# digital_io.net
KiCad netlist of a schematic drawn in Altium Designer
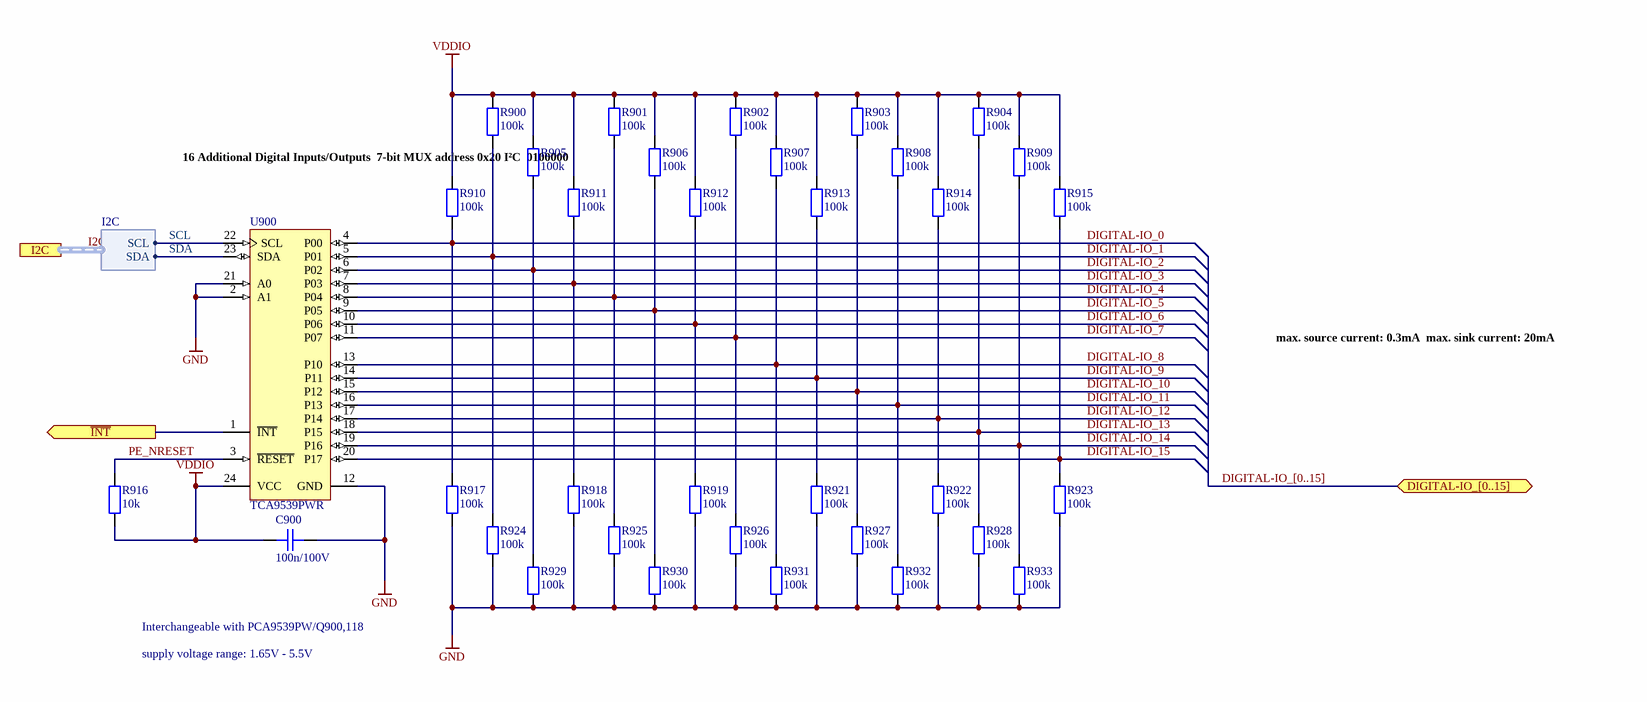
[diagram p0: digital_io.SchDoc]

(export (version "E")
  (design (tool "Eeschema 10.0.6"))
  (components
    (comp (ref "C900")
      (value "100n/100V")
      (footprint "CAPC1608X08N")
      (description "MLCC")
      (fields (field (name "PART NUMBER") "gen_C_ceramic_100n_100V_X7R_0603"))
      (libsource (lib "OE750") (part "C"))
    )
    (comp (ref "R900")
      (value "100k")
      (footprint "RESC1608X05N")
      (description "SMD Resistor 100k 0603")
      (fields (field (name "PART NUMBER") "gen_R_100k_0603") (field (name "TOLERANCE") "1%"))
      (libsource (lib "OE750") (part "R"))
    )
    (comp (ref "R901")
      (value "100k")
      (footprint "RESC1608X05N")
      (description "SMD Resistor 100k 0603")
      (fields (field (name "PART NUMBER") "gen_R_100k_0603") (field (name "TOLERANCE") "1%"))
      (libsource (lib "OE750") (part "R"))
    )
    (comp (ref "R902")
      (value "100k")
      (footprint "RESC1608X05N")
      (description "SMD Resistor 100k 0603")
      (fields (field (name "PART NUMBER") "gen_R_100k_0603") (field (name "TOLERANCE") "1%"))
      (libsource (lib "OE750") (part "R"))
    )
    (comp (ref "R903")
      (value "100k")
      (footprint "RESC1608X05N")
      (description "SMD Resistor 100k 0603")
      (fields (field (name "PART NUMBER") "gen_R_100k_0603") (field (name "TOLERANCE") "1%"))
      (libsource (lib "OE750") (part "R"))
    )
    (comp (ref "R904")
      (value "100k")
      (footprint "RESC1608X05N")
      (description "SMD Resistor 100k 0603")
      (fields (field (name "PART NUMBER") "gen_R_100k_0603") (field (name "TOLERANCE") "1%"))
      (libsource (lib "OE750") (part "R"))
    )
    (comp (ref "R905")
      (value "100k")
      (footprint "RESC1608X05N")
      (description "SMD Resistor 100k 0603")
      (fields (field (name "PART NUMBER") "gen_R_100k_0603") (field (name "TOLERANCE") "1%"))
      (libsource (lib "OE750") (part "R"))
    )
    (comp (ref "R906")
      (value "100k")
      (footprint "RESC1608X05N")
      (description "SMD Resistor 100k 0603")
      (fields (field (name "PART NUMBER") "gen_R_100k_0603") (field (name "TOLERANCE") "1%"))
      (libsource (lib "OE750") (part "R"))
    )
    (comp (ref "R907")
      (value "100k")
      (footprint "RESC1608X05N")
      (description "SMD Resistor 100k 0603")
      (fields (field (name "PART NUMBER") "gen_R_100k_0603") (field (name "TOLERANCE") "1%"))
      (libsource (lib "OE750") (part "R"))
    )
    (comp (ref "R908")
      (value "100k")
      (footprint "RESC1608X05N")
      (description "SMD Resistor 100k 0603")
      (fields (field (name "PART NUMBER") "gen_R_100k_0603") (field (name "TOLERANCE") "1%"))
      (libsource (lib "OE750") (part "R"))
    )
    (comp (ref "R909")
      (value "100k")
      (footprint "RESC1608X05N")
      (description "SMD Resistor 100k 0603")
      (fields (field (name "PART NUMBER") "gen_R_100k_0603") (field (name "TOLERANCE") "1%"))
      (libsource (lib "OE750") (part "R"))
    )
    (comp (ref "R910")
      (value "100k")
      (footprint "RESC1608X05N")
      (description "SMD Resistor 100k 0603")
      (fields (field (name "PART NUMBER") "gen_R_100k_0603") (field (name "TOLERANCE") "1%"))
      (libsource (lib "OE750") (part "R"))
    )
    (comp (ref "R911")
      (value "100k")
      (footprint "RESC1608X05N")
      (description "SMD Resistor 100k 0603")
      (fields (field (name "PART NUMBER") "gen_R_100k_0603") (field (name "TOLERANCE") "1%"))
      (libsource (lib "OE750") (part "R"))
    )
    (comp (ref "R912")
      (value "100k")
      (footprint "RESC1608X05N")
      (description "SMD Resistor 100k 0603")
      (fields (field (name "PART NUMBER") "gen_R_100k_0603") (field (name "TOLERANCE") "1%"))
      (libsource (lib "OE750") (part "R"))
    )
    (comp (ref "R913")
      (value "100k")
      (footprint "RESC1608X05N")
      (description "SMD Resistor 100k 0603")
      (fields (field (name "PART NUMBER") "gen_R_100k_0603") (field (name "TOLERANCE") "1%"))
      (libsource (lib "OE750") (part "R"))
    )
    (comp (ref "R914")
      (value "100k")
      (footprint "RESC1608X05N")
      (description "SMD Resistor 100k 0603")
      (fields (field (name "PART NUMBER") "gen_R_100k_0603") (field (name "TOLERANCE") "1%"))
      (libsource (lib "OE750") (part "R"))
    )
    (comp (ref "R915")
      (value "100k")
      (footprint "RESC1608X05N")
      (description "SMD Resistor 100k 0603")
      (fields (field (name "PART NUMBER") "gen_R_100k_0603") (field (name "TOLERANCE") "1%"))
      (libsource (lib "OE750") (part "R"))
    )
    (comp (ref "R916")
      (value "10k")
      (footprint "RESC1608X05N")
      (description "SMD Resistor 10k 0603")
      (fields (field (name "PART NUMBER") "gen_R_10k_0603") (field (name "TOLERANCE") "1%"))
      (libsource (lib "OE750") (part "R"))
    )
    (comp (ref "R917")
      (value "100k")
      (footprint "RESC1608X05N")
      (description "SMD Resistor 100k 0603")
      (fields (field (name "PART NUMBER") "gen_R_100k_0603") (field (name "TOLERANCE") "1%"))
      (libsource (lib "OE750") (part "R"))
    )
    (comp (ref "R918")
      (value "100k")
      (footprint "RESC1608X05N")
      (description "SMD Resistor 100k 0603")
      (fields (field (name "PART NUMBER") "gen_R_100k_0603") (field (name "TOLERANCE") "1%"))
      (libsource (lib "OE750") (part "R"))
    )
    (comp (ref "R919")
      (value "100k")
      (footprint "RESC1608X05N")
      (description "SMD Resistor 100k 0603")
      (fields (field (name "PART NUMBER") "gen_R_100k_0603") (field (name "TOLERANCE") "1%"))
      (libsource (lib "OE750") (part "R"))
    )
    (comp (ref "R921")
      (value "100k")
      (footprint "RESC1608X05N")
      (description "SMD Resistor 100k 0603")
      (fields (field (name "PART NUMBER") "gen_R_100k_0603") (field (name "TOLERANCE") "1%"))
      (libsource (lib "OE750") (part "R"))
    )
    (comp (ref "R922")
      (value "100k")
      (footprint "RESC1608X05N")
      (description "SMD Resistor 100k 0603")
      (fields (field (name "PART NUMBER") "gen_R_100k_0603") (field (name "TOLERANCE") "1%"))
      (libsource (lib "OE750") (part "R"))
    )
    (comp (ref "R923")
      (value "100k")
      (footprint "RESC1608X05N")
      (description "SMD Resistor 100k 0603")
      (fields (field (name "PART NUMBER") "gen_R_100k_0603") (field (name "TOLERANCE") "1%"))
      (libsource (lib "OE750") (part "R"))
    )
    (comp (ref "R924")
      (value "100k")
      (footprint "RESC1608X05N")
      (description "SMD Resistor 100k 0603")
      (fields (field (name "PART NUMBER") "gen_R_100k_0603") (field (name "TOLERANCE") "1%"))
      (libsource (lib "OE750") (part "R"))
    )
    (comp (ref "R925")
      (value "100k")
      (footprint "RESC1608X05N")
      (description "SMD Resistor 100k 0603")
      (fields (field (name "PART NUMBER") "gen_R_100k_0603") (field (name "TOLERANCE") "1%"))
      (libsource (lib "OE750") (part "R"))
    )
    (comp (ref "R926")
      (value "100k")
      (footprint "RESC1608X05N")
      (description "SMD Resistor 100k 0603")
      (fields (field (name "PART NUMBER") "gen_R_100k_0603") (field (name "TOLERANCE") "1%"))
      (libsource (lib "OE750") (part "R"))
    )
    (comp (ref "R927")
      (value "100k")
      (footprint "RESC1608X05N")
      (description "SMD Resistor 100k 0603")
      (fields (field (name "PART NUMBER") "gen_R_100k_0603") (field (name "TOLERANCE") "1%"))
      (libsource (lib "OE750") (part "R"))
    )
    (comp (ref "R928")
      (value "100k")
      (footprint "RESC1608X05N")
      (description "SMD Resistor 100k 0603")
      (fields (field (name "PART NUMBER") "gen_R_100k_0603") (field (name "TOLERANCE") "1%"))
      (libsource (lib "OE750") (part "R"))
    )
    (comp (ref "R929")
      (value "100k")
      (footprint "RESC1608X05N")
      (description "SMD Resistor 100k 0603")
      (fields (field (name "PART NUMBER") "gen_R_100k_0603") (field (name "TOLERANCE") "1%"))
      (libsource (lib "OE750") (part "R"))
    )
    (comp (ref "R930")
      (value "100k")
      (footprint "RESC1608X05N")
      (description "SMD Resistor 100k 0603")
      (fields (field (name "PART NUMBER") "gen_R_100k_0603") (field (name "TOLERANCE") "1%"))
      (libsource (lib "OE750") (part "R"))
    )
    (comp (ref "R931")
      (value "100k")
      (footprint "RESC1608X05N")
      (description "SMD Resistor 100k 0603")
      (fields (field (name "PART NUMBER") "gen_R_100k_0603") (field (name "TOLERANCE") "1%"))
      (libsource (lib "OE750") (part "R"))
    )
    (comp (ref "R932")
      (value "100k")
      (footprint "RESC1608X05N")
      (description "SMD Resistor 100k 0603")
      (fields (field (name "PART NUMBER") "gen_R_100k_0603") (field (name "TOLERANCE") "1%"))
      (libsource (lib "OE750") (part "R"))
    )
    (comp (ref "R933")
      (value "100k")
      (footprint "RESC1608X05N")
      (description "SMD Resistor 100k 0603")
      (fields (field (name "PART NUMBER") "gen_R_100k_0603") (field (name "TOLERANCE") "1%"))
      (libsource (lib "OE750") (part "R"))
    )
    (comp (ref "U900")
      (value "TCA9539PWR")
      (footprint "PW0024A_M")
      (fields (field (name "MANUFACTURER") "Texas Instruments"))
      (libsource (lib "Altium Content Vault") (part "TI-TCA9539-TSSOP_PW-24"))
    )
  )
  (nets
    (net (code "2") (name "/DIGITAL-IO_0") (class "Default")
      (node (ref "R910") (pin "1") (pinfunction "1_1") (pintype "passive"))
      (node (ref "R917") (pin "2") (pinfunction "2_2") (pintype "passive"))
      (node (ref "U900") (pin "4") (pinfunction "P00_4") (pintype "bidirectional"))
    )
    (net (code "3") (name "/DIGITAL-IO_1") (class "Default")
      (node (ref "R900") (pin "1") (pinfunction "1_1") (pintype "passive"))
      (node (ref "R924") (pin "2") (pinfunction "2_2") (pintype "passive"))
      (node (ref "U900") (pin "5") (pinfunction "P01_5") (pintype "bidirectional"))
    )
    (net (code "4") (name "/DIGITAL-IO_2") (class "Default")
      (node (ref "R905") (pin "1") (pinfunction "1_1") (pintype "passive"))
      (node (ref "R929") (pin "2") (pinfunction "2_2") (pintype "passive"))
      (node (ref "U900") (pin "6") (pinfunction "P02_6") (pintype "bidirectional"))
    )
    (net (code "5") (name "/DIGITAL-IO_3") (class "Default")
      (node (ref "R911") (pin "1") (pinfunction "1_1") (pintype "passive"))
      (node (ref "R918") (pin "2") (pinfunction "2_2") (pintype "passive"))
      (node (ref "U900") (pin "7") (pinfunction "P03_7") (pintype "bidirectional"))
    )
    (net (code "6") (name "/DIGITAL-IO_4") (class "Default")
      (node (ref "R901") (pin "1") (pinfunction "1_1") (pintype "passive"))
      (node (ref "R925") (pin "2") (pinfunction "2_2") (pintype "passive"))
      (node (ref "U900") (pin "8") (pinfunction "P04_8") (pintype "bidirectional"))
    )
    (net (code "7") (name "/DIGITAL-IO_5") (class "Default")
      (node (ref "R906") (pin "1") (pinfunction "1_1") (pintype "passive"))
      (node (ref "R930") (pin "2") (pinfunction "2_2") (pintype "passive"))
      (node (ref "U900") (pin "9") (pinfunction "P05_9") (pintype "bidirectional"))
    )
    (net (code "8") (name "/DIGITAL-IO_6") (class "Default")
      (node (ref "R912") (pin "1") (pinfunction "1_1") (pintype "passive"))
      (node (ref "R919") (pin "2") (pinfunction "2_2") (pintype "passive"))
      (node (ref "U900") (pin "10") (pinfunction "P06_10") (pintype "bidirectional"))
    )
    (net (code "9") (name "/DIGITAL-IO_7") (class "Default")
      (node (ref "R902") (pin "1") (pinfunction "1_1") (pintype "passive"))
      (node (ref "R926") (pin "2") (pinfunction "2_2") (pintype "passive"))
      (node (ref "U900") (pin "11") (pinfunction "P07_11") (pintype "bidirectional"))
    )
    (net (code "10") (name "/DIGITAL-IO_8") (class "Default")
      (node (ref "R907") (pin "1") (pinfunction "1_1") (pintype "passive"))
      (node (ref "R931") (pin "2") (pinfunction "2_2") (pintype "passive"))
      (node (ref "U900") (pin "13") (pinfunction "P10_13") (pintype "bidirectional"))
    )
    (net (code "11") (name "/DIGITAL-IO_9") (class "Default")
      (node (ref "R913") (pin "1") (pinfunction "1_1") (pintype "passive"))
      (node (ref "R921") (pin "2") (pinfunction "2_2") (pintype "passive"))
      (node (ref "U900") (pin "14") (pinfunction "P11_14") (pintype "bidirectional"))
    )
    (net (code "12") (name "/DIGITAL-IO_10") (class "Default")
      (node (ref "R903") (pin "1") (pinfunction "1_1") (pintype "passive"))
      (node (ref "R927") (pin "2") (pinfunction "2_2") (pintype "passive"))
      (node (ref "U900") (pin "15") (pinfunction "P12_15") (pintype "bidirectional"))
    )
    (net (code "13") (name "/DIGITAL-IO_11") (class "Default")
      (node (ref "R908") (pin "1") (pinfunction "1_1") (pintype "passive"))
      (node (ref "R932") (pin "2") (pinfunction "2_2") (pintype "passive"))
      (node (ref "U900") (pin "16") (pinfunction "P13_16") (pintype "bidirectional"))
    )
    (net (code "14") (name "/DIGITAL-IO_12") (class "Default")
      (node (ref "R914") (pin "1") (pinfunction "1_1") (pintype "passive"))
      (node (ref "R922") (pin "2") (pinfunction "2_2") (pintype "passive"))
      (node (ref "U900") (pin "17") (pinfunction "P14_17") (pintype "bidirectional"))
    )
    (net (code "15") (name "/DIGITAL-IO_13") (class "Default")
      (node (ref "R904") (pin "1") (pinfunction "1_1") (pintype "passive"))
      (node (ref "R928") (pin "2") (pinfunction "2_2") (pintype "passive"))
      (node (ref "U900") (pin "18") (pinfunction "P15_18") (pintype "bidirectional"))
    )
    (net (code "16") (name "/DIGITAL-IO_14") (class "Default")
      (node (ref "R909") (pin "1") (pinfunction "1_1") (pintype "passive"))
      (node (ref "R933") (pin "2") (pinfunction "2_2") (pintype "passive"))
      (node (ref "U900") (pin "19") (pinfunction "P16_19") (pintype "bidirectional"))
    )
    (net (code "17") (name "/DIGITAL-IO_15") (class "Default")
      (node (ref "R915") (pin "1") (pinfunction "1_1") (pintype "passive"))
      (node (ref "R923") (pin "2") (pinfunction "2_2") (pintype "passive"))
      (node (ref "U900") (pin "20") (pinfunction "P17_20") (pintype "bidirectional"))
    )
    (net (code "20") (name "/PE_NRESET") (class "Default")
      (node (ref "R916") (pin "2") (pinfunction "2_2") (pintype "passive"))
      (node (ref "U900") (pin "3") (pinfunction "~{RESET}_3") (pintype "input"))
    )
    (net (code "21") (name "/SCL") (class "Default")
      (node (ref "U900") (pin "22") (pinfunction "SCL_22") (pintype "input"))
    )
    (net (code "22") (name "/SDA") (class "Default")
      (node (ref "U900") (pin "23") (pinfunction "SDA_23") (pintype "bidirectional"))
    )
    (net (code "23") (name "/~{INT}") (class "Default")
      (node (ref "U900") (pin "1") (pinfunction "~{INT}_1") (pintype "open_collector"))
    )
    (net (code "24") (name "GND") (class "Default")
      (node (ref "C900") (pin "1") (pinfunction "1_1") (pintype "passive"))
      (node (ref "R917") (pin "1") (pinfunction "1_1") (pintype "passive"))
      (node (ref "R918") (pin "1") (pinfunction "1_1") (pintype "passive"))
      (node (ref "R919") (pin "1") (pinfunction "1_1") (pintype "passive"))
      (node (ref "R921") (pin "1") (pinfunction "1_1") (pintype "passive"))
      (node (ref "R922") (pin "1") (pinfunction "1_1") (pintype "passive"))
      (node (ref "R923") (pin "1") (pinfunction "1_1") (pintype "passive"))
      (node (ref "R924") (pin "1") (pinfunction "1_1") (pintype "passive"))
      (node (ref "R925") (pin "1") (pinfunction "1_1") (pintype "passive"))
      (node (ref "R926") (pin "1") (pinfunction "1_1") (pintype "passive"))
      (node (ref "R927") (pin "1") (pinfunction "1_1") (pintype "passive"))
      (node (ref "R928") (pin "1") (pinfunction "1_1") (pintype "passive"))
      (node (ref "R929") (pin "1") (pinfunction "1_1") (pintype "passive"))
      (node (ref "R930") (pin "1") (pinfunction "1_1") (pintype "passive"))
      (node (ref "R931") (pin "1") (pinfunction "1_1") (pintype "passive"))
      (node (ref "R932") (pin "1") (pinfunction "1_1") (pintype "passive"))
      (node (ref "R933") (pin "1") (pinfunction "1_1") (pintype "passive"))
      (node (ref "U900") (pin "12") (pinfunction "GND_12") (pintype "power_in"))
      (node (ref "U900") (pin "2") (pinfunction "A1_2") (pintype "input"))
      (node (ref "U900") (pin "21") (pinfunction "A0_21") (pintype "input"))
    )
    (net (code "25") (name "VDDIO") (class "Default")
      (node (ref "C900") (pin "2") (pinfunction "2_2") (pintype "passive"))
      (node (ref "R900") (pin "2") (pinfunction "2_2") (pintype "passive"))
      (node (ref "R901") (pin "2") (pinfunction "2_2") (pintype "passive"))
      (node (ref "R902") (pin "2") (pinfunction "2_2") (pintype "passive"))
      (node (ref "R903") (pin "2") (pinfunction "2_2") (pintype "passive"))
      (node (ref "R904") (pin "2") (pinfunction "2_2") (pintype "passive"))
      (node (ref "R905") (pin "2") (pinfunction "2_2") (pintype "passive"))
      (node (ref "R906") (pin "2") (pinfunction "2_2") (pintype "passive"))
      (node (ref "R907") (pin "2") (pinfunction "2_2") (pintype "passive"))
      (node (ref "R908") (pin "2") (pinfunction "2_2") (pintype "passive"))
      (node (ref "R909") (pin "2") (pinfunction "2_2") (pintype "passive"))
      (node (ref "R910") (pin "2") (pinfunction "2_2") (pintype "passive"))
      (node (ref "R911") (pin "2") (pinfunction "2_2") (pintype "passive"))
      (node (ref "R912") (pin "2") (pinfunction "2_2") (pintype "passive"))
      (node (ref "R913") (pin "2") (pinfunction "2_2") (pintype "passive"))
      (node (ref "R914") (pin "2") (pinfunction "2_2") (pintype "passive"))
      (node (ref "R915") (pin "2") (pinfunction "2_2") (pintype "passive"))
      (node (ref "R916") (pin "1") (pinfunction "1_1") (pintype "passive"))
      (node (ref "U900") (pin "24") (pinfunction "VCC_24") (pintype "power_in"))
    )
  )
)
